# const_current_x4.net
KiCad netlist of a schematic drawn in EAGLE
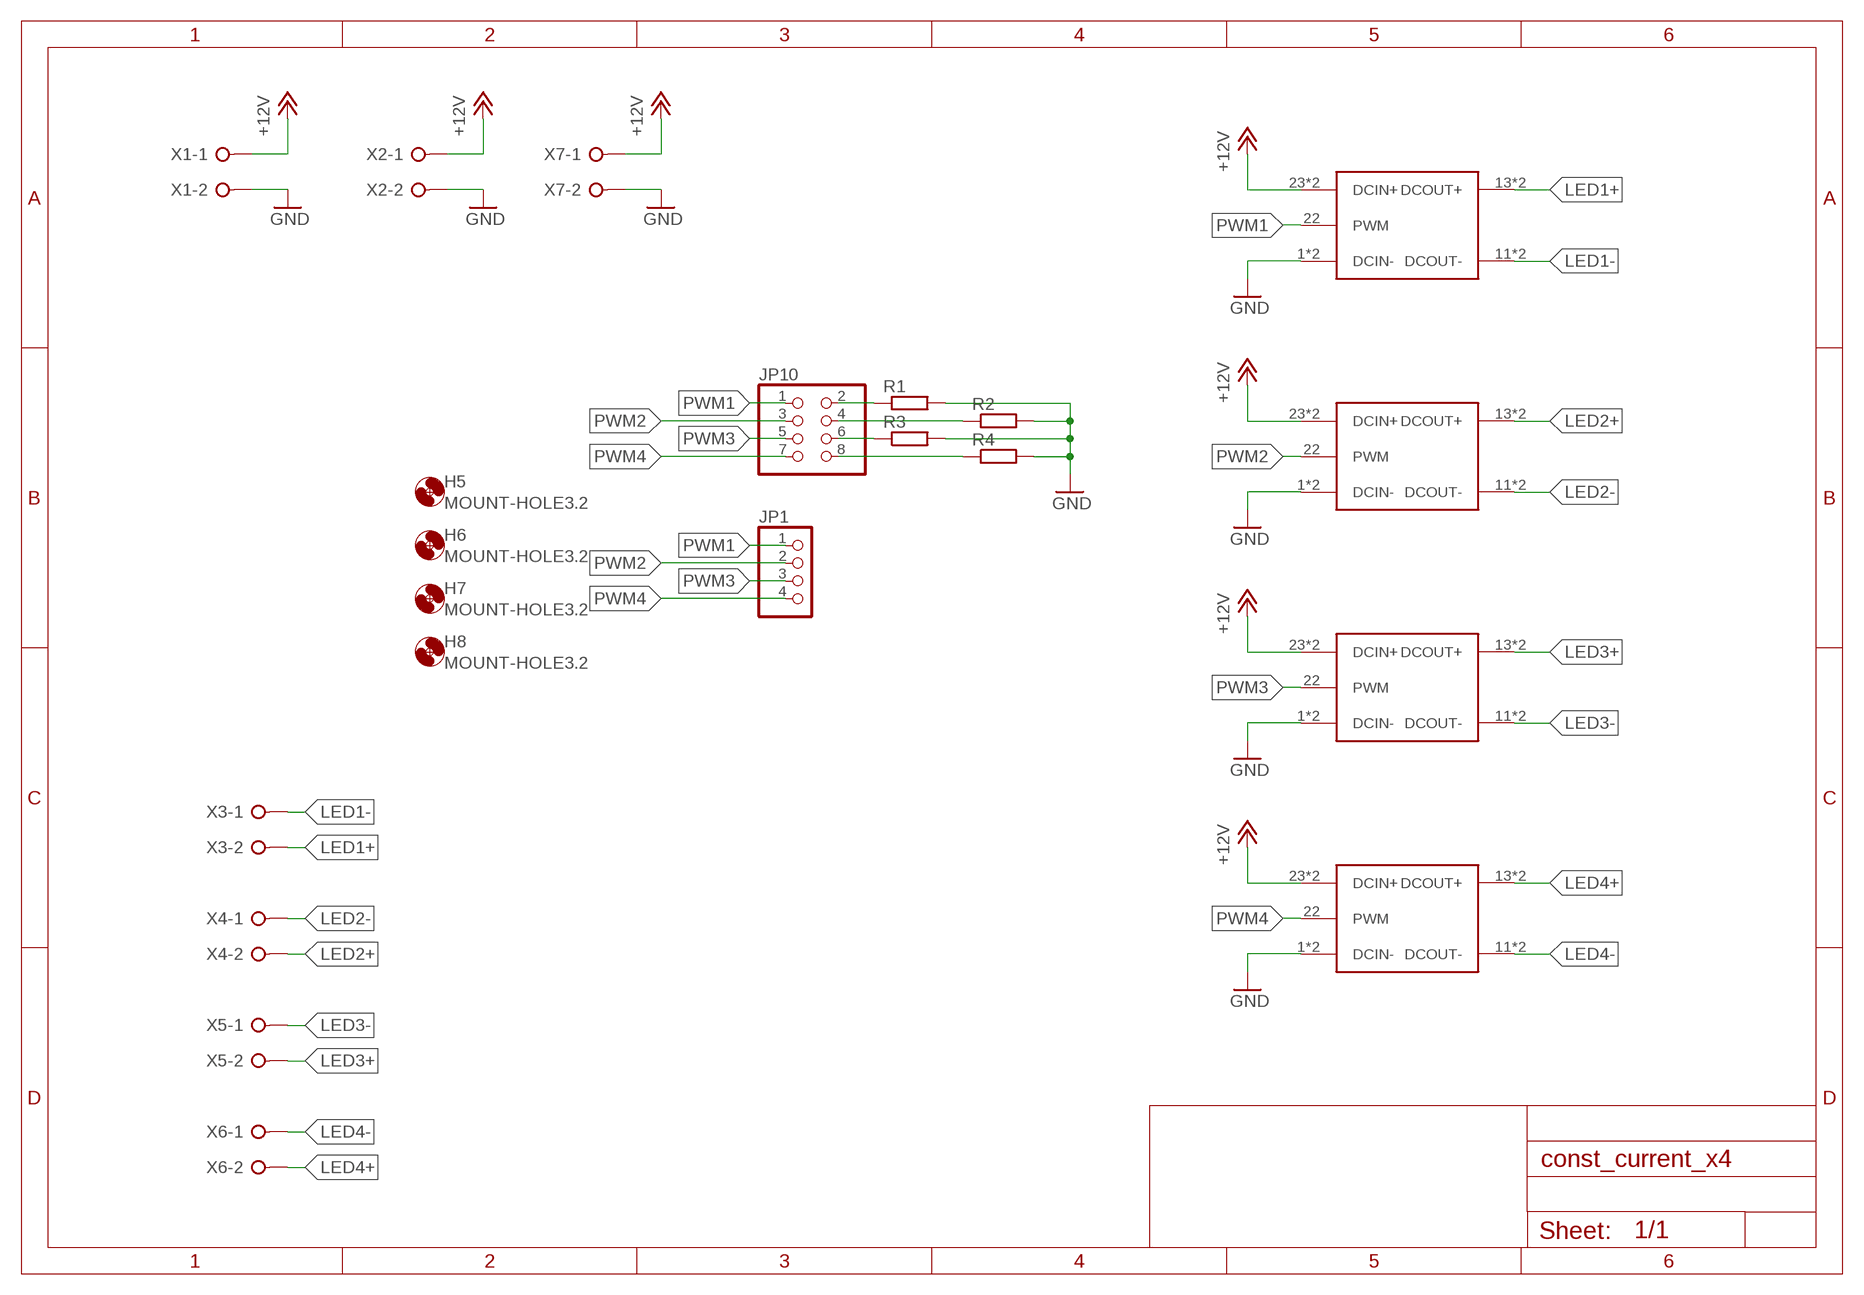
[diagram p0: schematic, sheet 1]

(export (version "E")
  (design (tool "Eeschema 10.0.6"))
  (components
    (comp (ref "H5")
      (value "MOUNT-HOLE3.2")
      (footprint "eagle-import:3,2")
      (libsource (lib "eagle-import") (part "MOUNT-HOLE3.2"))
    )
    (comp (ref "H6")
      (value "MOUNT-HOLE3.2")
      (footprint "eagle-import:3,2")
      (libsource (lib "eagle-import") (part "MOUNT-HOLE3.2"))
    )
    (comp (ref "H7")
      (value "MOUNT-HOLE3.2")
      (footprint "eagle-import:3,2")
      (libsource (lib "eagle-import") (part "MOUNT-HOLE3.2"))
    )
    (comp (ref "H8")
      (value "MOUNT-HOLE3.2")
      (footprint "eagle-import:3,2")
      (libsource (lib "eagle-import") (part "MOUNT-HOLE3.2"))
    )
    (comp (ref "JP1")
      (value "PINHD-1X4")
      (footprint "eagle-import:1X04")
      (libsource (lib "eagle-import") (part "PINHD-1X4"))
    )
    (comp (ref "JP10")
      (value "PINHD-2X4")
      (footprint "eagle-import:2X04")
      (libsource (lib "eagle-import") (part "PINHD-2X4"))
    )
    (comp (ref "R1")
      (value "R-EU_0207/10")
      (footprint "eagle-import:0207_10")
      (libsource (lib "eagle-import") (part "R-EU_0207/10"))
    )
    (comp (ref "R2")
      (value "R-EU_0207/10")
      (footprint "eagle-import:0207_10")
      (libsource (lib "eagle-import") (part "R-EU_0207/10"))
    )
    (comp (ref "R3")
      (value "R-EU_0207/10")
      (footprint "eagle-import:0207_10")
      (libsource (lib "eagle-import") (part "R-EU_0207/10"))
    )
    (comp (ref "R4")
      (value "R-EU_0207/10")
      (footprint "eagle-import:0207_10")
      (libsource (lib "eagle-import") (part "R-EU_0207/10"))
    )
    (comp (ref "U$5")
      (value "LDD_H")
      (footprint "eagle-import:LDD_H")
      (libsource (lib "eagle-import") (part "LDD_H"))
    )
    (comp (ref "U$6")
      (value "LDD_H")
      (footprint "eagle-import:LDD_H")
      (libsource (lib "eagle-import") (part "LDD_H"))
    )
    (comp (ref "U$7")
      (value "LDD_H")
      (footprint "eagle-import:LDD_H")
      (libsource (lib "eagle-import") (part "LDD_H"))
    )
    (comp (ref "U$8")
      (value "LDD_H")
      (footprint "eagle-import:LDD_H")
      (libsource (lib "eagle-import") (part "LDD_H"))
    )
    (comp (ref "X1")
      (value "W237-02P")
      (footprint "eagle-import:W237-132")
      (libsource (lib "eagle-import") (part "W237-02P"))
    )
    (comp (ref "X2")
      (value "W237-02P")
      (footprint "eagle-import:W237-132")
      (libsource (lib "eagle-import") (part "W237-02P"))
    )
    (comp (ref "X3")
      (value "W237-02P")
      (footprint "eagle-import:W237-132")
      (libsource (lib "eagle-import") (part "W237-02P"))
    )
    (comp (ref "X4")
      (value "W237-02P")
      (footprint "eagle-import:W237-132")
      (libsource (lib "eagle-import") (part "W237-02P"))
    )
    (comp (ref "X5")
      (value "W237-02P")
      (footprint "eagle-import:W237-132")
      (libsource (lib "eagle-import") (part "W237-02P"))
    )
    (comp (ref "X6")
      (value "W237-02P")
      (footprint "eagle-import:W237-132")
      (libsource (lib "eagle-import") (part "W237-02P"))
    )
    (comp (ref "X7")
      (value "W237-02P")
      (footprint "eagle-import:W237-132")
      (libsource (lib "eagle-import") (part "W237-02P"))
    )
  )
  (nets
    (net (code "1") (name "+12V") (class "Default")
      (node (ref "U$5") (pin "23") (pinfunction "DCIN+_23") (pintype "input"))
      (node (ref "U$5") (pin "24") (pinfunction "DCIN+_24") (pintype "input"))
      (node (ref "U$6") (pin "23") (pinfunction "DCIN+_23") (pintype "input"))
      (node (ref "U$6") (pin "24") (pinfunction "DCIN+_24") (pintype "input"))
      (node (ref "U$7") (pin "23") (pinfunction "DCIN+_23") (pintype "input"))
      (node (ref "U$7") (pin "24") (pinfunction "DCIN+_24") (pintype "input"))
      (node (ref "U$8") (pin "23") (pinfunction "DCIN+_23") (pintype "input"))
      (node (ref "U$8") (pin "24") (pinfunction "DCIN+_24") (pintype "input"))
      (node (ref "X1") (pin "1") (pinfunction "KL_1") (pintype "passive"))
      (node (ref "X2") (pin "1") (pinfunction "KL_1") (pintype "passive"))
      (node (ref "X7") (pin "1") (pinfunction "KL_1") (pintype "passive"))
    )
    (net (code "2") (name "GND") (class "Default")
      (node (ref "R1") (pin "2") (pinfunction "2_2") (pintype "passive"))
      (node (ref "R2") (pin "2") (pinfunction "2_2") (pintype "passive"))
      (node (ref "R3") (pin "2") (pinfunction "2_2") (pintype "passive"))
      (node (ref "R4") (pin "2") (pinfunction "2_2") (pintype "passive"))
      (node (ref "U$5") (pin "1") (pinfunction "DCIN-_1") (pintype "input"))
      (node (ref "U$5") (pin "2") (pinfunction "DCIN-_2") (pintype "input"))
      (node (ref "U$6") (pin "1") (pinfunction "DCIN-_1") (pintype "input"))
      (node (ref "U$6") (pin "2") (pinfunction "DCIN-_2") (pintype "input"))
      (node (ref "U$7") (pin "1") (pinfunction "DCIN-_1") (pintype "input"))
      (node (ref "U$7") (pin "2") (pinfunction "DCIN-_2") (pintype "input"))
      (node (ref "U$8") (pin "1") (pinfunction "DCIN-_1") (pintype "input"))
      (node (ref "U$8") (pin "2") (pinfunction "DCIN-_2") (pintype "input"))
      (node (ref "X1") (pin "2") (pinfunction "KL_2") (pintype "passive"))
      (node (ref "X2") (pin "2") (pinfunction "KL_2") (pintype "passive"))
      (node (ref "X7") (pin "2") (pinfunction "KL_2") (pintype "passive"))
    )
    (net (code "3") (name "LED1+") (class "Default")
      (node (ref "U$5") (pin "13") (pinfunction "DCOUT+_13") (pintype "output"))
      (node (ref "U$5") (pin "14") (pinfunction "DCOUT+_14") (pintype "output"))
      (node (ref "X3") (pin "2") (pinfunction "KL_2") (pintype "passive"))
    )
    (net (code "4") (name "LED1-") (class "Default")
      (node (ref "U$5") (pin "11") (pinfunction "DCOUT-_11") (pintype "output"))
      (node (ref "U$5") (pin "12") (pinfunction "DCOUT-_12") (pintype "output"))
      (node (ref "X3") (pin "1") (pinfunction "KL_1") (pintype "passive"))
    )
    (net (code "5") (name "LED2+") (class "Default")
      (node (ref "U$6") (pin "13") (pinfunction "DCOUT+_13") (pintype "output"))
      (node (ref "U$6") (pin "14") (pinfunction "DCOUT+_14") (pintype "output"))
      (node (ref "X4") (pin "2") (pinfunction "KL_2") (pintype "passive"))
    )
    (net (code "6") (name "LED2-") (class "Default")
      (node (ref "U$6") (pin "11") (pinfunction "DCOUT-_11") (pintype "output"))
      (node (ref "U$6") (pin "12") (pinfunction "DCOUT-_12") (pintype "output"))
      (node (ref "X4") (pin "1") (pinfunction "KL_1") (pintype "passive"))
    )
    (net (code "7") (name "LED3+") (class "Default")
      (node (ref "U$7") (pin "13") (pinfunction "DCOUT+_13") (pintype "output"))
      (node (ref "U$7") (pin "14") (pinfunction "DCOUT+_14") (pintype "output"))
      (node (ref "X5") (pin "2") (pinfunction "KL_2") (pintype "passive"))
    )
    (net (code "8") (name "LED3-") (class "Default")
      (node (ref "U$7") (pin "11") (pinfunction "DCOUT-_11") (pintype "output"))
      (node (ref "U$7") (pin "12") (pinfunction "DCOUT-_12") (pintype "output"))
      (node (ref "X5") (pin "1") (pinfunction "KL_1") (pintype "passive"))
    )
    (net (code "9") (name "LED4+") (class "Default")
      (node (ref "U$8") (pin "13") (pinfunction "DCOUT+_13") (pintype "output"))
      (node (ref "U$8") (pin "14") (pinfunction "DCOUT+_14") (pintype "output"))
      (node (ref "X6") (pin "2") (pinfunction "KL_2") (pintype "passive"))
    )
    (net (code "10") (name "LED4-") (class "Default")
      (node (ref "U$8") (pin "11") (pinfunction "DCOUT-_11") (pintype "output"))
      (node (ref "U$8") (pin "12") (pinfunction "DCOUT-_12") (pintype "output"))
      (node (ref "X6") (pin "1") (pinfunction "KL_1") (pintype "passive"))
    )
    (net (code "11") (name "Net-(JP10-Pad2)") (class "Default")
      (node (ref "JP10") (pin "2") (pinfunction "2_2") (pintype "passive"))
      (node (ref "R1") (pin "1") (pinfunction "1_1") (pintype "passive"))
    )
    (net (code "12") (name "Net-(JP10-Pad4)") (class "Default")
      (node (ref "JP10") (pin "4") (pinfunction "4_4") (pintype "passive"))
      (node (ref "R2") (pin "1") (pinfunction "1_1") (pintype "passive"))
    )
    (net (code "13") (name "Net-(JP10-Pad6)") (class "Default")
      (node (ref "JP10") (pin "6") (pinfunction "6_6") (pintype "passive"))
      (node (ref "R3") (pin "1") (pinfunction "1_1") (pintype "passive"))
    )
    (net (code "14") (name "Net-(JP10-Pad8)") (class "Default")
      (node (ref "JP10") (pin "8") (pinfunction "8_8") (pintype "passive"))
      (node (ref "R4") (pin "1") (pinfunction "1_1") (pintype "passive"))
    )
    (net (code "15") (name "PWM1") (class "Default")
      (node (ref "JP1") (pin "1") (pinfunction "1_1") (pintype "passive"))
      (node (ref "JP10") (pin "1") (pinfunction "1_1") (pintype "passive"))
      (node (ref "U$5") (pin "22") (pinfunction "PWM_22") (pintype "bidirectional"))
    )
    (net (code "16") (name "PWM2") (class "Default")
      (node (ref "JP1") (pin "2") (pinfunction "2_2") (pintype "passive"))
      (node (ref "JP10") (pin "3") (pinfunction "3_3") (pintype "passive"))
      (node (ref "U$6") (pin "22") (pinfunction "PWM_22") (pintype "bidirectional"))
    )
    (net (code "17") (name "PWM3") (class "Default")
      (node (ref "JP1") (pin "3") (pinfunction "3_3") (pintype "passive"))
      (node (ref "JP10") (pin "5") (pinfunction "5_5") (pintype "passive"))
      (node (ref "U$7") (pin "22") (pinfunction "PWM_22") (pintype "bidirectional"))
    )
    (net (code "18") (name "PWM4") (class "Default")
      (node (ref "JP1") (pin "4") (pinfunction "4_4") (pintype "passive"))
      (node (ref "JP10") (pin "7") (pinfunction "7_7") (pintype "passive"))
      (node (ref "U$8") (pin "22") (pinfunction "PWM_22") (pintype "bidirectional"))
    )
  )
)
